# TPS6513x.net
KiCad netlist of a schematic drawn in Altium Designer
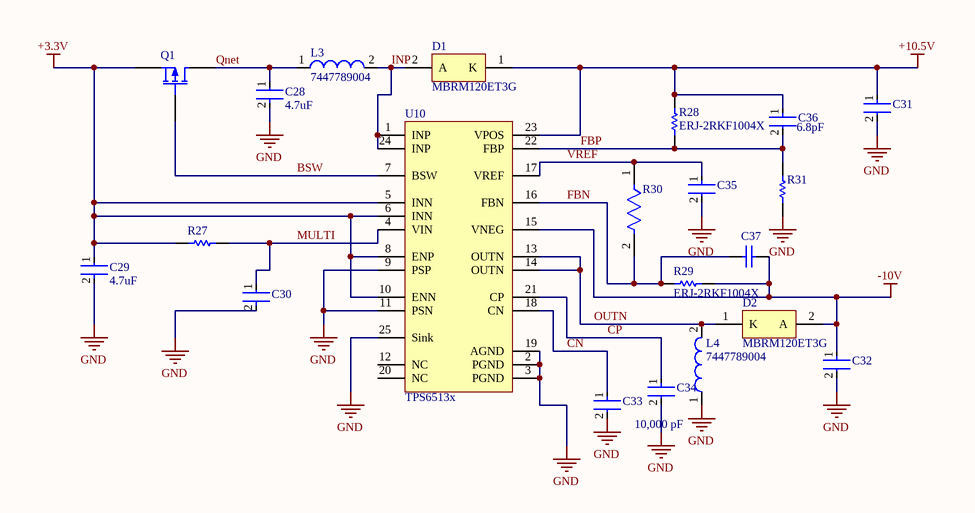
[diagram p0: TPS6513x.SchDoc]

(export (version "E")
  (design (tool "Eeschema 10.0.6"))
  (components
    (comp (ref "C28")
      (value "4.7uF")
      (footprint "FP-GRM15-MFG")
      (description "CAP CER 0.1UF 16V X7R 0402")
      (fields (field (name "MANUFACTURER PART NUMBER") "GRM155R71C104KA88D") (field (name "TOLERANCE") "10%"))
      (libsource (lib "Altium Content Vault") (part "236180d848d6139a670b325ea6854c9"))
    )
    (comp (ref "C29")
      (value "4.7uF")
      (footprint "FP-GRM15-MFG")
      (description "CAP CER 0.1UF 16V X7R 0402")
      (fields (field (name "MANUFACTURER PART NUMBER") "GRM155R71C104KA88D") (field (name "TOLERANCE") "10%"))
      (libsource (lib "Altium Content Vault") (part "236180d848d6139a670b325ea6854c9"))
    )
    (comp (ref "C30")
      (value "GRM155R71C104KA88D")
      (footprint "FP-GRM15-MFG")
      (description "CAP CER 0.1UF 16V X7R 0402")
      (fields
        (field (name "TOLERANCE") "10%")
        (field (name "OCTOPART") "https://octopart.com/grm155r71c104ka88d-murata-196880")
      )
      (libsource (lib "Altium Content Vault") (part "236180d848d6139a670b325ea6854c9"))
    )
    (comp (ref "C31")
      (value "CL05A226MQ5QUNC")
      (footprint "FP-CL746-IPC_C")
      (description "Cap Ceramic 22uF 6.3V X5R ±20% SMD 0402 +85°C Paper T/R")
      (fields (field (name "TOLERANCE") "20%"))
      (libsource (lib "Altium Content Vault") (part "b4654b650e69147ec39a6b967a45e02"))
    )
    (comp (ref "C32")
      (value "CL05A226MQ5QUNC")
      (footprint "FP-CL746-IPC_C")
      (description "Cap Ceramic 22uF 6.3V X5R ±20% SMD 0402 +85°C Paper T/R")
      (fields (field (name "TOLERANCE") "20%"))
      (libsource (lib "Altium Content Vault") (part "b4654b650e69147ec39a6b967a45e02"))
    )
    (comp (ref "C33")
      (value "GRM155R71H472KA01D")
      (footprint "FP-GRM155-0_05-IPC_B")
      (description "Chip Multilayer Ceramic Capacitors for General Purpose, 0402, 4700pF, X7R, 15%, 10%, 50V")
      (fields (field (name "VOLTAGE") "50V") (field (name "TOLERANCE") "10%"))
      (libsource (lib "Altium Content Vault") (part "02cd4be3c70576c341d710602a673aa"))
    )
    (comp (ref "C34")
      (value "10,000 pF")
      (footprint "Yemet_0603")
      (description "C0402 10,000 pF X7R 5.00% 16 V")
      (fields (field (name "MANUFACTURER PART NUMBER") "C0402C103J4RAC") (field (name "TOLERANCE") "0.05"))
      (libsource (lib "Miscellaneous Devices") (part "b4654b650e69147ec39a6b967a45e02"))
    )
    (comp (ref "C35")
      (value "GRM155R71C224KA12D")
      (footprint "FP-GRM155-0_05-IPC_C")
      (description "Chip Multilayer Ceramic Capacitors for General Purpose, 0402, 0.22uF, X7R, 15%, 10%, 16V")
      (fields (field (name "VOLTAGE") "16V") (field (name "TOLERANCE") "10%"))
      (libsource (lib "Altium Content Vault") (part "02cd4be3c70576c341d710602a673aa"))
    )
    (comp (ref "C36")
      (value "CGA1A2C0G1E6R8D030BA")
      (footprint "885012007027")
      (description "Cap Ceramic 6.8pF 25V C0G 0.5pF Pad SMD 0201 125°C Automotive T/R")
      (fields (field (name "CAPACITANCE") "6.8pF"))
      (libsource (lib "Miscellaneous Devices") (part "b4654b650e69147ec39a6b967a45e02"))
    )
    (comp (ref "C37")
      (value "GRM1555C1H7R5CA01D")
      (footprint "CAPC1005X55X25LL05T10")
      (fields (field (name "MANUFACTURER") "Murata"))
      (libsource (lib "Altium Content Vault") (part "CAP"))
    )
    (comp (ref "D1")
      (value "MBRM120ET3G")
      (footprint "ONSC-POWERMITE-2-457-04_D_V")
      (description "Schottky Power Rectifier, 2-Pin Powermite, Pb-Free, Tape and Reel")
      (fields (field (name "MANUFACTURER") "On Semiconductor"))
      (libsource (lib "Altium Content Vault") (part "ONSC-D-K1A2-2_A"))
    )
    (comp (ref "D2")
      (value "MBRM120ET3G")
      (footprint "ONSC-POWERMITE-2-457-04_D_V")
      (description "Schottky Power Rectifier, 2-Pin Powermite, Pb-Free, Tape and Reel")
      (fields (field (name "MANUFACTURER") "On Semiconductor"))
      (libsource (lib "") (part "ONSC-D-K1A2-2_A_1"))
    )
    (comp (ref "L3")
      (value "7447789004")
      (footprint "WE-PD-S-PB")
      (description "SMD-Shielded Power Inductor WE-PD, L=4.70 µH")
      (fields (field (name "MANUFACTURER") "Wuerth Elektronik"))
      (libsource (lib "Altium Content Vault") (part "PAS-IND-INDUCTOR-2"))
    )
    (comp (ref "L4")
      (value "7447789004")
      (footprint "WE-PD-S-PB")
      (description "SMD-Shielded Power Inductor WE-PD, L=4.70 µH")
      (fields (field (name "MANUFACTURER") "Wuerth Elektronik"))
      (libsource (lib "Altium Content Vault") (part "PAS-IND-INDUCTOR-2"))
    )
    (comp (ref "Q1")
      (value "Comment")
      (footprint "TPS6513_pcb:PCBComponent_1")
      (description "P-Channel MOSFET")
      (fields (field (name "PUBLISHER") "Altium Limited"))
      (libsource (lib "Miscellaneous Devices") (part "MOSFET-P"))
    )
    (comp (ref "R27")
      (value "ERJ-2RKF1000X")
      (footprint "RESC1005X40X25LL05T05")
      (description "Chip Resistor, 100 Ohm, +/- 1%, 100 mW, -55 to 155 degC, 0402 (1005 Metric), RoHS, Tape and Reel")
      (fields (field (name "MANUFACTURER") "Basic Passives") (field (name "TOLERANCE") "1%"))
      (libsource (lib "Altium Content Vault") (part "RES-2"))
    )
    (comp (ref "R28")
      (value "ERJ-2RKF1004X")
      (footprint "RESC1005X40X25LL05T05")
      (description "Chip Resistor, 1 MOhm, +/- 1%, 100 mW, -55 to 155 degC, 0402 (1005 Metric), RoHS, Tape and Reel")
      (fields (field (name "TOLERANCE") "1%") (field (name "MANUFACTURER") "Basic Passives"))
      (libsource (lib "Altium Content Vault") (part "RES-2"))
    )
    (comp (ref "R29")
      (value "ERJ-2RKF1004X")
      (footprint "RESC1005X40X25LL05T05")
      (description "Chip Resistor, 1 MOhm, +/- 1%, 100 mW, -55 to 155 degC, 0402 (1005 Metric), RoHS, Tape and Reel")
      (fields (field (name "TOLERANCE") "1%") (field (name "MANUFACTURER") "Basic Passives"))
      (libsource (lib "Altium Content Vault") (part "RES-2"))
    )
    (comp (ref "R30")
      (value "CRCW0402121KFKED")
      (footprint "FP-CRCW0402-e3-MFG")
      (description "RES Thick Film, 121kΩ, 1%, 0.063W, 100ppm/°C, 0402")
      (fields (field (name "TOLERANCE") "1%"))
      (libsource (lib "Altium Content Vault") (part "1029c3af85768c4190bb7ad29bc67b5"))
    )
    (comp (ref "R31")
      (value "ERJ-2RKF1303X")
      (footprint "RESC1005X40X25NL05T05")
      (fields (field (name "MANUFACTURER") "Panasonic"))
      (libsource (lib "Altium Content Vault") (part "RES"))
    )
    (comp (ref "U10")
      (value "TPS6513x")
      (footprint "TPS6513final")
      (fields (field (name "PARTNUMBER") "TPS65130RGER") (field (name "MANUFACTURER") "Texas Instruments"))
      (libsource (lib "Buck_and_Inverter") (part "TI-TPS65130RGE24-2450X2450TP"))
    )
  )
  (nets
    (net (code "1") (name "+3.3V") (class "Default")
      (node (ref "C29") (pin "1") (pinfunction "1_1") (pintype "passive"))
      (node (ref "Q1") (pin "3") (pinfunction "S_3") (pintype "passive"))
      (node (ref "R27") (pin "1") (pinfunction "1_1") (pintype "passive"))
      (node (ref "U10") (pin "10") (pinfunction "ENN_10") (pintype "passive"))
      (node (ref "U10") (pin "5") (pinfunction "INN_5") (pintype "passive"))
      (node (ref "U10") (pin "6") (pinfunction "INN_6") (pintype "passive"))
      (node (ref "U10") (pin "8") (pinfunction "ENP_8") (pintype "passive"))
    )
    (net (code "2") (name "+10.5V") (class "Default")
      (node (ref "C31") (pin "1") (pinfunction "1_1") (pintype "passive"))
      (node (ref "C36") (pin "1") (pinfunction "1_1") (pintype "passive"))
      (node (ref "D1") (pin "1") (pinfunction "K_1") (pintype "passive"))
      (node (ref "R28") (pin "2") (pinfunction "2_2") (pintype "passive"))
      (node (ref "U10") (pin "23") (pinfunction "VPOS_23") (pintype "passive"))
    )
    (net (code "3") (name "-10V") (class "Default")
      (node (ref "C32") (pin "1") (pinfunction "1_1") (pintype "passive"))
      (node (ref "C37") (pin "2") (pinfunction "2_2") (pintype "passive"))
      (node (ref "D2") (pin "2") (pinfunction "A_2") (pintype "passive"))
      (node (ref "R29") (pin "1") (pinfunction "1_1") (pintype "passive"))
      (node (ref "U10") (pin "15") (pinfunction "VNEG_15") (pintype "passive"))
    )
    (net (code "4") (name "/BSW") (class "Default")
      (node (ref "Q1") (pin "2") (pinfunction "G_2") (pintype "passive"))
      (node (ref "U10") (pin "7") (pinfunction "BSW_7") (pintype "passive"))
    )
    (net (code "5") (name "/CN") (class "Default")
      (node (ref "C33") (pin "1") (pinfunction "1_1") (pintype "passive"))
      (node (ref "U10") (pin "18") (pinfunction "CN_18") (pintype "passive"))
    )
    (net (code "6") (name "/CP") (class "Default")
      (node (ref "C34") (pin "1") (pinfunction "1_1") (pintype "passive"))
      (node (ref "U10") (pin "21") (pinfunction "CP_21") (pintype "passive"))
    )
    (net (code "7") (name "/FBN") (class "Default")
      (node (ref "C37") (pin "1") (pinfunction "1_1") (pintype "passive"))
      (node (ref "R29") (pin "2") (pinfunction "2_2") (pintype "passive"))
      (node (ref "R30") (pin "2") (pinfunction "2_2") (pintype "passive"))
      (node (ref "U10") (pin "16") (pinfunction "FBN_16") (pintype "passive"))
    )
    (net (code "8") (name "/FBP") (class "Default")
      (node (ref "C36") (pin "2") (pinfunction "2_2") (pintype "passive"))
      (node (ref "R28") (pin "1") (pinfunction "1_1") (pintype "passive"))
      (node (ref "R31") (pin "2") (pinfunction "2_2") (pintype "passive"))
      (node (ref "U10") (pin "22") (pinfunction "FBP_22") (pintype "passive"))
    )
    (net (code "9") (name "/INP") (class "Default")
      (node (ref "D1") (pin "2") (pinfunction "A_2") (pintype "passive"))
      (node (ref "L3") (pin "2") (pinfunction "2_2") (pintype "passive"))
      (node (ref "U10") (pin "1") (pinfunction "INP_1") (pintype "passive"))
      (node (ref "U10") (pin "24") (pinfunction "INP_24") (pintype "passive"))
    )
    (net (code "10") (name "/MULTI") (class "Default")
      (node (ref "C30") (pin "1") (pinfunction "1_1") (pintype "passive"))
      (node (ref "R27") (pin "2") (pinfunction "2_2") (pintype "passive"))
      (node (ref "U10") (pin "4") (pinfunction "VIN_4") (pintype "passive"))
    )
    (net (code "11") (name "/OUTN") (class "Default")
      (node (ref "D2") (pin "1") (pinfunction "K_1") (pintype "passive"))
      (node (ref "L4") (pin "2") (pinfunction "2_2") (pintype "passive"))
      (node (ref "U10") (pin "13") (pinfunction "OUTN_13") (pintype "passive"))
      (node (ref "U10") (pin "14") (pinfunction "OUTN_14") (pintype "passive"))
    )
    (net (code "12") (name "/Qnet") (class "Default")
      (node (ref "C28") (pin "1") (pinfunction "1_1") (pintype "passive"))
      (node (ref "L3") (pin "1") (pinfunction "1_1") (pintype "passive"))
      (node (ref "Q1") (pin "1") (pinfunction "D_1") (pintype "passive"))
    )
    (net (code "13") (name "/VREF") (class "Default")
      (node (ref "C35") (pin "1") (pinfunction "1_1") (pintype "passive"))
      (node (ref "R30") (pin "1") (pinfunction "1_1") (pintype "passive"))
      (node (ref "U10") (pin "17") (pinfunction "VREF_17") (pintype "passive"))
    )
    (net (code "14") (name "GND") (class "Default")
      (node (ref "C28") (pin "2") (pinfunction "2_2") (pintype "passive"))
      (node (ref "C29") (pin "2") (pinfunction "2_2") (pintype "passive"))
      (node (ref "C30") (pin "2") (pinfunction "2_2") (pintype "passive"))
      (node (ref "C31") (pin "2") (pinfunction "2_2") (pintype "passive"))
      (node (ref "C32") (pin "2") (pinfunction "2_2") (pintype "passive"))
      (node (ref "C33") (pin "2") (pinfunction "2_2") (pintype "passive"))
      (node (ref "C34") (pin "2") (pinfunction "2_2") (pintype "passive"))
      (node (ref "C35") (pin "2") (pinfunction "2_2") (pintype "passive"))
      (node (ref "L4") (pin "1") (pinfunction "1_1") (pintype "passive"))
      (node (ref "R31") (pin "1") (pinfunction "1_1") (pintype "passive"))
      (node (ref "U10") (pin "11") (pinfunction "PSN_11") (pintype "passive"))
      (node (ref "U10") (pin "19") (pinfunction "AGND_19") (pintype "passive"))
      (node (ref "U10") (pin "2") (pinfunction "PGND_2") (pintype "passive"))
      (node (ref "U10") (pin "25") (pinfunction "Sink_25") (pintype "passive"))
      (node (ref "U10") (pin "3") (pinfunction "PGND_3") (pintype "passive"))
      (node (ref "U10") (pin "9") (pinfunction "PSP_9") (pintype "passive"))
    )
    (net (code "15") (name "unconnected-(U10-NC-Pad12)") (class "Default")
      (node (ref "U10") (pin "12") (pinfunction "NC_12") (pintype "passive"))
    )
    (net (code "16") (name "unconnected-(U10-NC-Pad20)") (class "Default")
      (node (ref "U10") (pin "20") (pinfunction "NC_20") (pintype "passive"))
    )
  )
)
